# CHAIRI2C.net
KiCad netlist of a schematic drawn in EAGLE
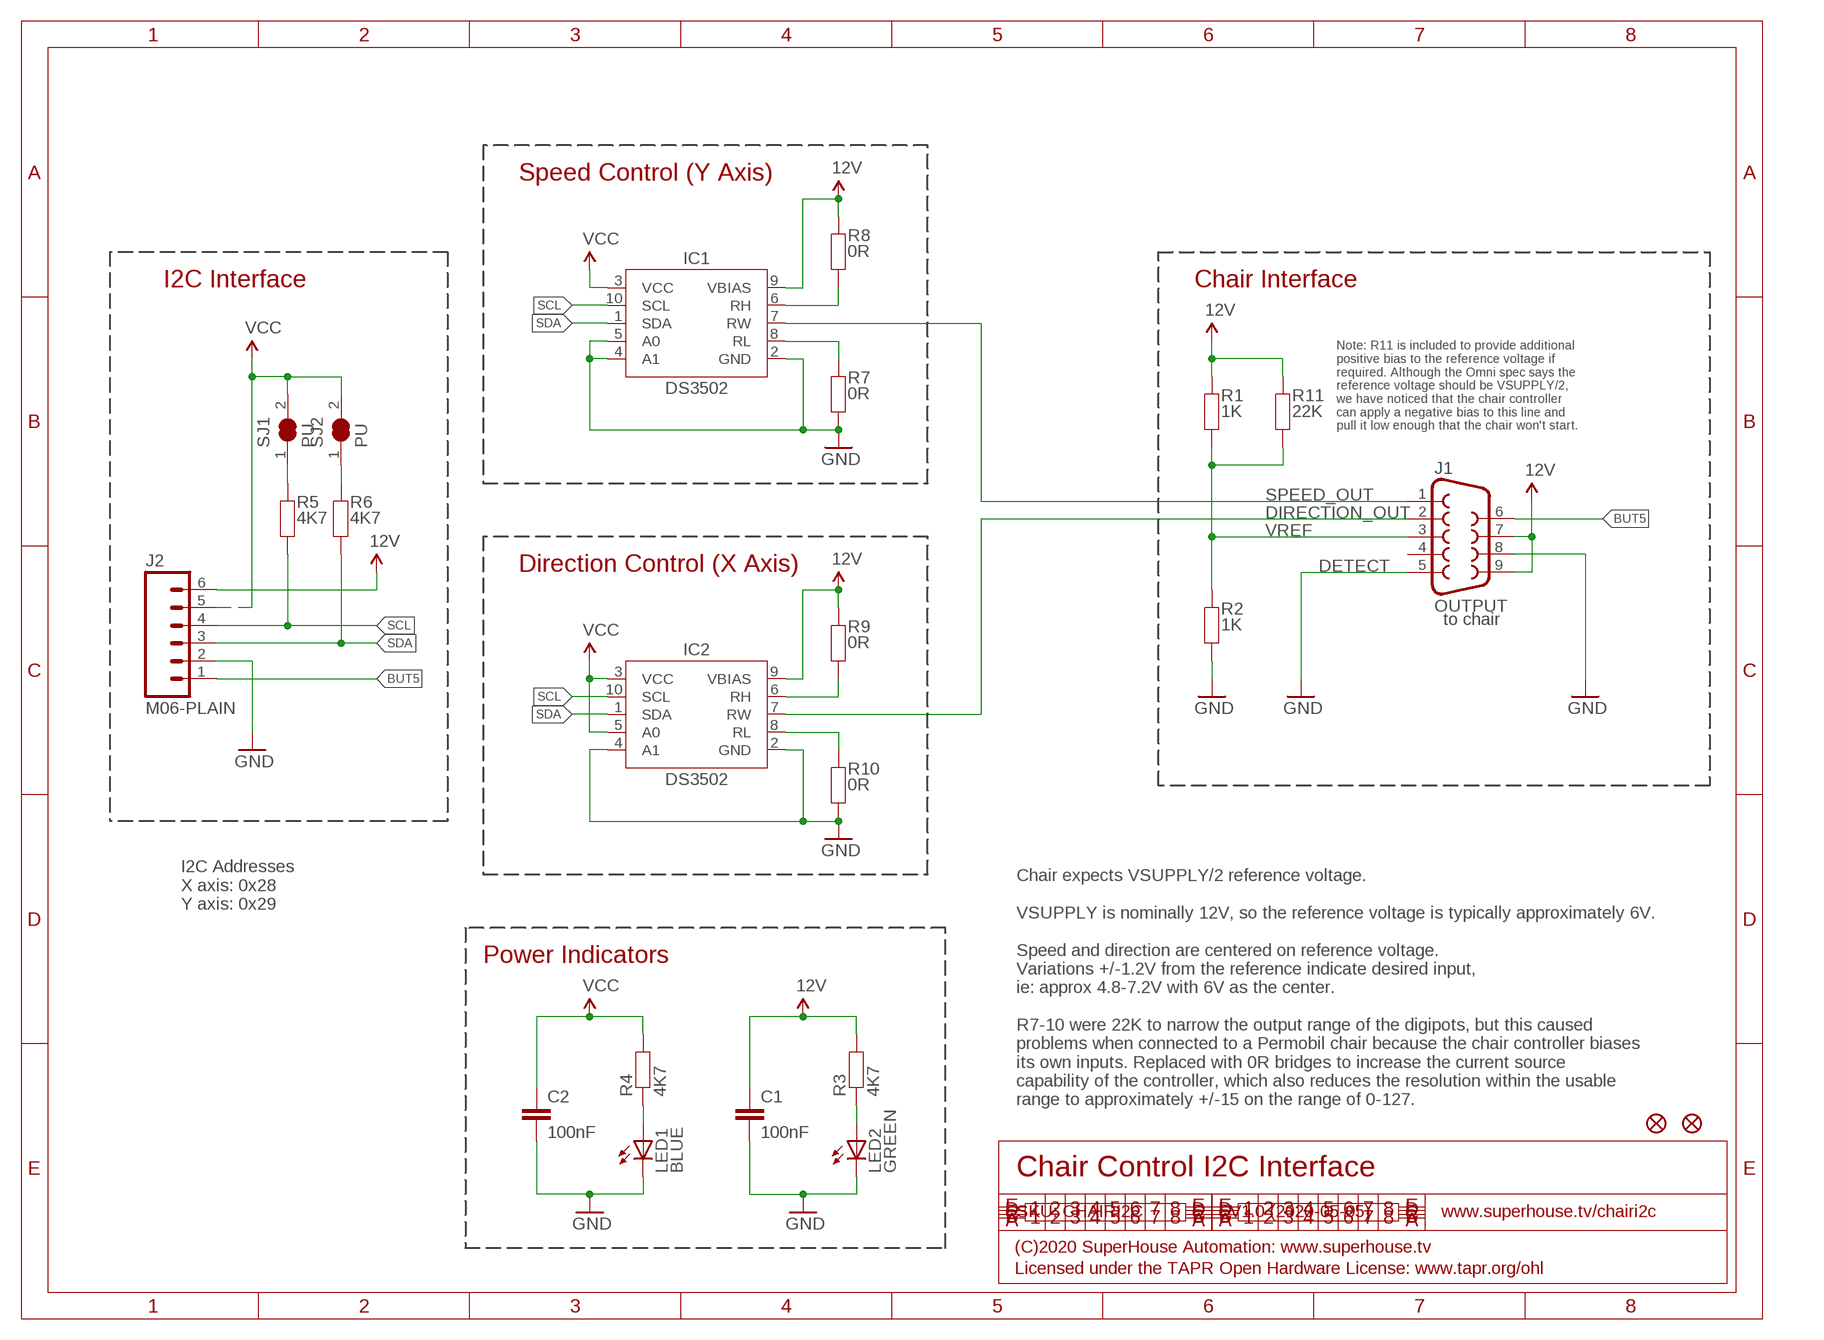
[diagram p0: schematic, sheet 1]

(export (version "E")
  (design (tool "Eeschema 10.0.6"))
  (components
    (comp (ref "C1")
      (value "100nF")
      (footprint "eagle-import:C0603")
      (libsource (lib "eagle-import") (part "CAP0603"))
    )
    (comp (ref "C2")
      (value "100nF")
      (footprint "eagle-import:C0603")
      (libsource (lib "eagle-import") (part "CAP0603"))
    )
    (comp (ref "FID1")
      (value "FIDUCIAL1X2.5")
      (footprint "eagle-import:FIDUCIAL-1X2.5")
      (libsource (lib "eagle-import") (part "FIDUCIAL1X2.5"))
    )
    (comp (ref "FID2")
      (value "FIDUCIAL1X2.5")
      (footprint "eagle-import:FIDUCIAL-1X2.5")
      (libsource (lib "eagle-import") (part "FIDUCIAL1X2.5"))
    )
    (comp (ref "IC1")
      (value "DS3502")
      (footprint "eagle-import:MSOP10")
      (libsource (lib "eagle-import") (part "DS3502"))
    )
    (comp (ref "IC2")
      (value "DS3502")
      (footprint "eagle-import:MSOP10")
      (libsource (lib "eagle-import") (part "DS3502"))
    )
    (comp (ref "J1")
      (value "OUTPUT")
      (footprint "eagle-import:DB9-PCB-SOCKET")
      (libsource (lib "eagle-import") (part "DB9-PCB-SOCKET"))
    )
    (comp (ref "J2")
      (value "M06-PLAIN")
      (footprint "eagle-import:1X06")
      (libsource (lib "eagle-import") (part "M06-PLAIN"))
    )
    (comp (ref "LED1")
      (value "BLUE")
      (footprint "eagle-import:LED-0603")
      (libsource (lib "eagle-import") (part "LED0603"))
    )
    (comp (ref "LED2")
      (value "GREEN")
      (footprint "eagle-import:LED-0603")
      (libsource (lib "eagle-import") (part "LED0603"))
    )
    (comp (ref "R1")
      (value "1K")
      (footprint "eagle-import:R0603")
      (libsource (lib "eagle-import") (part "RESISTOR0603"))
    )
    (comp (ref "R2")
      (value "1K")
      (footprint "eagle-import:R0603")
      (libsource (lib "eagle-import") (part "RESISTOR0603"))
    )
    (comp (ref "R3")
      (value "4K7")
      (footprint "eagle-import:R0603")
      (libsource (lib "eagle-import") (part "RESISTOR0603"))
    )
    (comp (ref "R4")
      (value "4K7")
      (footprint "eagle-import:R0603")
      (libsource (lib "eagle-import") (part "RESISTOR0603"))
    )
    (comp (ref "R5")
      (value "4K7")
      (footprint "eagle-import:R0603")
      (libsource (lib "eagle-import") (part "RESISTOR0603"))
    )
    (comp (ref "R6")
      (value "4K7")
      (footprint "eagle-import:R0603")
      (libsource (lib "eagle-import") (part "RESISTOR0603"))
    )
    (comp (ref "R7")
      (value "0R")
      (footprint "eagle-import:R0603")
      (libsource (lib "eagle-import") (part "RESISTOR0603"))
    )
    (comp (ref "R8")
      (value "0R")
      (footprint "eagle-import:R0603")
      (libsource (lib "eagle-import") (part "RESISTOR0603"))
    )
    (comp (ref "R9")
      (value "0R")
      (footprint "eagle-import:R0603")
      (libsource (lib "eagle-import") (part "RESISTOR0603"))
    )
    (comp (ref "R10")
      (value "0R")
      (footprint "eagle-import:R0603")
      (libsource (lib "eagle-import") (part "RESISTOR0603"))
    )
    (comp (ref "R11")
      (value "22K")
      (footprint "eagle-import:R0603")
      (libsource (lib "eagle-import") (part "RESISTOR0603"))
    )
    (comp (ref "SJ1")
      (value "PU")
      (footprint "eagle-import:SJC")
      (libsource (lib "eagle-import") (part "SJC-NORMAL"))
    )
    (comp (ref "SJ2")
      (value "PU")
      (footprint "eagle-import:SJC")
      (libsource (lib "eagle-import") (part "SJC-NORMAL"))
    )
  )
  (nets
    (net (code "1") (name "/DIRECTION_OUT") (class "Default")
      (node (ref "IC2") (pin "7") (pinfunction "RW_7") (pintype "passive"))
      (node (ref "J1") (pin "2") (pinfunction "2_2") (pintype "passive"))
    )
    (net (code "2") (name "/SPEED_OUT") (class "Default")
      (node (ref "IC1") (pin "7") (pinfunction "RW_7") (pintype "passive"))
      (node (ref "J1") (pin "1") (pinfunction "1_1") (pintype "passive"))
    )
    (net (code "3") (name "/VREF") (class "Default")
      (node (ref "J1") (pin "3") (pinfunction "3_3") (pintype "passive"))
      (node (ref "R1") (pin "1") (pinfunction "1_1") (pintype "passive"))
      (node (ref "R11") (pin "1") (pinfunction "1_1") (pintype "passive"))
      (node (ref "R2") (pin "2") (pinfunction "2_2") (pintype "passive"))
    )
    (net (code "4") (name "12V") (class "Default")
      (node (ref "C1") (pin "1") (pinfunction "1_1") (pintype "passive"))
      (node (ref "IC1") (pin "9") (pinfunction "VBIAS_9") (pintype "power_in"))
      (node (ref "IC2") (pin "9") (pinfunction "VBIAS_9") (pintype "power_in"))
      (node (ref "J1") (pin "7") (pinfunction "7_7") (pintype "passive"))
      (node (ref "J1") (pin "9") (pinfunction "9_9") (pintype "passive"))
      (node (ref "J2") (pin "6") (pinfunction "6_6") (pintype "passive"))
      (node (ref "R1") (pin "2") (pinfunction "2_2") (pintype "passive"))
      (node (ref "R11") (pin "2") (pinfunction "2_2") (pintype "passive"))
      (node (ref "R3") (pin "2") (pinfunction "2_2") (pintype "passive"))
      (node (ref "R8") (pin "2") (pinfunction "2_2") (pintype "passive"))
      (node (ref "R9") (pin "2") (pinfunction "2_2") (pintype "passive"))
    )
    (net (code "5") (name "BUT5") (class "Default")
      (node (ref "J1") (pin "6") (pinfunction "6_6") (pintype "passive"))
      (node (ref "J2") (pin "1") (pinfunction "1_1") (pintype "passive"))
    )
    (net (code "6") (name "GND") (class "Default")
      (node (ref "C1") (pin "2") (pinfunction "2_2") (pintype "passive"))
      (node (ref "C2") (pin "2") (pinfunction "2_2") (pintype "passive"))
      (node (ref "IC1") (pin "2") (pinfunction "GND_2") (pintype "power_in"))
      (node (ref "IC1") (pin "4") (pinfunction "A1_4") (pintype "input"))
      (node (ref "IC1") (pin "5") (pinfunction "A0_5") (pintype "input"))
      (node (ref "IC2") (pin "2") (pinfunction "GND_2") (pintype "power_in"))
      (node (ref "IC2") (pin "4") (pinfunction "A1_4") (pintype "input"))
      (node (ref "J1") (pin "5") (pinfunction "5_5") (pintype "passive"))
      (node (ref "J1") (pin "8") (pinfunction "8_8") (pintype "passive"))
      (node (ref "J2") (pin "2") (pinfunction "2_2") (pintype "passive"))
      (node (ref "LED1") (pin "C") (pinfunction "C_C") (pintype "passive"))
      (node (ref "LED2") (pin "C") (pinfunction "C_C") (pintype "passive"))
      (node (ref "R10") (pin "1") (pinfunction "1_1") (pintype "passive"))
      (node (ref "R2") (pin "1") (pinfunction "1_1") (pintype "passive"))
      (node (ref "R7") (pin "1") (pinfunction "1_1") (pintype "passive"))
    )
    (net (code "7") (name "Net-(IC1-RH)") (class "Default")
      (node (ref "IC1") (pin "6") (pinfunction "RH_6") (pintype "passive"))
      (node (ref "R8") (pin "1") (pinfunction "1_1") (pintype "passive"))
    )
    (net (code "8") (name "Net-(IC1-RL)") (class "Default")
      (node (ref "IC1") (pin "8") (pinfunction "RL_8") (pintype "passive"))
      (node (ref "R7") (pin "2") (pinfunction "2_2") (pintype "passive"))
    )
    (net (code "9") (name "Net-(IC2-RH)") (class "Default")
      (node (ref "IC2") (pin "6") (pinfunction "RH_6") (pintype "passive"))
      (node (ref "R9") (pin "1") (pinfunction "1_1") (pintype "passive"))
    )
    (net (code "10") (name "Net-(IC2-RL)") (class "Default")
      (node (ref "IC2") (pin "8") (pinfunction "RL_8") (pintype "passive"))
      (node (ref "R10") (pin "2") (pinfunction "2_2") (pintype "passive"))
    )
    (net (code "11") (name "Net-(LED1-PadA)") (class "Default")
      (node (ref "LED1") (pin "A") (pinfunction "A_A") (pintype "passive"))
      (node (ref "R4") (pin "1") (pinfunction "1_1") (pintype "passive"))
    )
    (net (code "12") (name "Net-(LED2-PadA)") (class "Default")
      (node (ref "LED2") (pin "A") (pinfunction "A_A") (pintype "passive"))
      (node (ref "R3") (pin "1") (pinfunction "1_1") (pintype "passive"))
    )
    (net (code "13") (name "Net-(R5-Pad2)") (class "Default")
      (node (ref "R5") (pin "2") (pinfunction "2_2") (pintype "passive"))
      (node (ref "SJ1") (pin "1") (pinfunction "1_1") (pintype "passive"))
    )
    (net (code "14") (name "Net-(R6-Pad2)") (class "Default")
      (node (ref "R6") (pin "2") (pinfunction "2_2") (pintype "passive"))
      (node (ref "SJ2") (pin "1") (pinfunction "1_1") (pintype "passive"))
    )
    (net (code "15") (name "SCL") (class "Default")
      (node (ref "IC1") (pin "10") (pinfunction "SCL_10") (pintype "input"))
      (node (ref "IC2") (pin "10") (pinfunction "SCL_10") (pintype "input"))
      (node (ref "J2") (pin "4") (pinfunction "4_4") (pintype "passive"))
      (node (ref "R5") (pin "1") (pinfunction "1_1") (pintype "passive"))
    )
    (net (code "16") (name "SDA") (class "Default")
      (node (ref "IC1") (pin "1") (pinfunction "SDA_1") (pintype "bidirectional"))
      (node (ref "IC2") (pin "1") (pinfunction "SDA_1") (pintype "bidirectional"))
      (node (ref "J2") (pin "3") (pinfunction "3_3") (pintype "passive"))
      (node (ref "R6") (pin "1") (pinfunction "1_1") (pintype "passive"))
    )
    (net (code "17") (name "VCC") (class "Default")
      (node (ref "C2") (pin "1") (pinfunction "1_1") (pintype "passive"))
      (node (ref "IC1") (pin "3") (pinfunction "VCC_3") (pintype "power_in"))
      (node (ref "IC2") (pin "3") (pinfunction "VCC_3") (pintype "power_in"))
      (node (ref "IC2") (pin "5") (pinfunction "A0_5") (pintype "input"))
      (node (ref "J2") (pin "5") (pinfunction "5_5") (pintype "passive"))
      (node (ref "R4") (pin "2") (pinfunction "2_2") (pintype "passive"))
      (node (ref "SJ1") (pin "2") (pinfunction "2_2") (pintype "passive"))
      (node (ref "SJ2") (pin "2") (pinfunction "2_2") (pintype "passive"))
    )
    (net (code "18") (name "unconnected-(J1-Pad4)") (class "Default")
      (node (ref "J1") (pin "4") (pinfunction "4_4") (pintype "passive"))
    )
  )
)
